# AMP_UN7_T.net
KiCad netlist of a schematic drawn in EAGLE
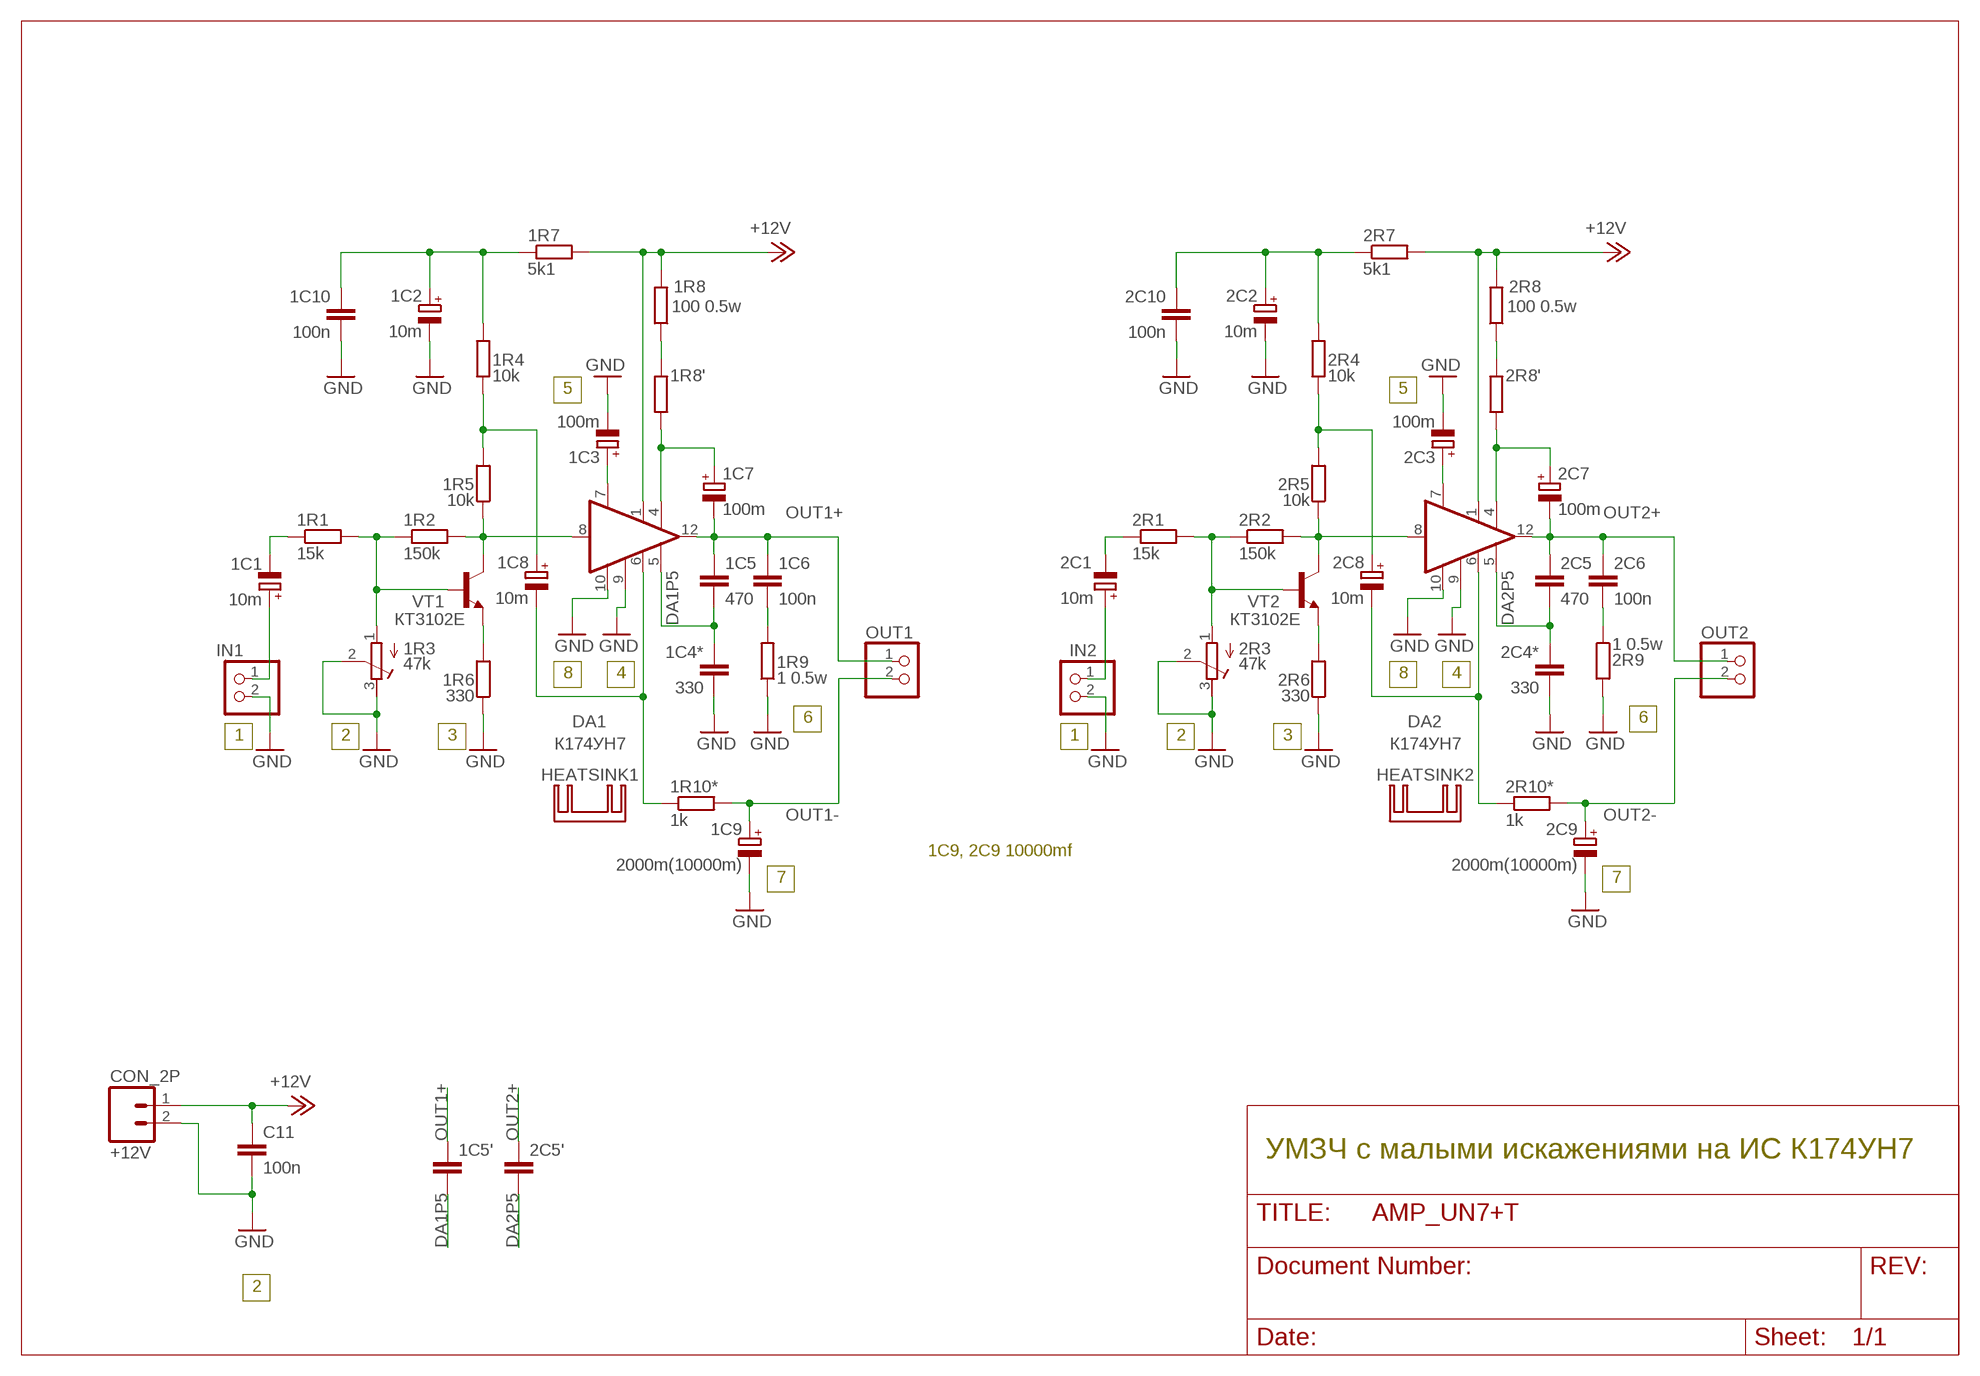
[diagram p0: schematic, sheet 1]

(export (version "E")
  (design (tool "Eeschema 10.0.6"))
  (components
    (comp (ref "+12V")
      (value "CON_2P")
      (footprint "eagle-import:CON_PWR_2PIN4MM")
      (libsource (lib "eagle-import") (part "CON_2P"))
    )
    (comp (ref "1C1")
      (value "10m")
      (footprint "eagle-import:E2,5-5")
      (libsource (lib "eagle-import") (part "CPOL-EUE2.5-5"))
    )
    (comp (ref "1C2")
      (value "10m")
      (footprint "eagle-import:E2,5-5")
      (libsource (lib "eagle-import") (part "CPOL-EUE2.5-5"))
    )
    (comp (ref "1C3")
      (value "100m")
      (footprint "eagle-import:E2,5-6")
      (libsource (lib "eagle-import") (part "CPOL-EUE2.5-6"))
    )
    (comp (ref "1C4*")
      (value "330")
      (footprint "eagle-import:C050-025X075")
      (libsource (lib "eagle-import") (part "C-EU050-025X075"))
    )
    (comp (ref "1C5")
      (value "470")
      (footprint "eagle-import:C050-030X075")
      (libsource (lib "eagle-import") (part "C-EU050-030X075"))
    )
    (comp (ref "1C5'")
      (value "C-EUC0805")
      (footprint "eagle-import:C0805")
      (libsource (lib "eagle-import") (part "C-EUC0805"))
    )
    (comp (ref "1C6")
      (value "100n")
      (footprint "eagle-import:C075-052X106")
      (libsource (lib "eagle-import") (part "C-EU075-052X106"))
    )
    (comp (ref "1C7")
      (value "100m")
      (footprint "eagle-import:E2,5-5")
      (libsource (lib "eagle-import") (part "CPOL-EUE2.5-5"))
    )
    (comp (ref "1C8")
      (value "10m")
      (footprint "eagle-import:E2,5-5")
      (libsource (lib "eagle-import") (part "CPOL-EUE2.5-5"))
    )
    (comp (ref "1C9")
      (value "2000m(10000m)")
      (footprint "eagle-import:E5-13")
      (libsource (lib "eagle-import") (part "CPOL-EUE5-13"))
    )
    (comp (ref "1C10")
      (value "100n")
      (footprint "eagle-import:C0805")
      (libsource (lib "eagle-import") (part "C-EUC0805"))
    )
    (comp (ref "1R1")
      (value "15k")
      (footprint "eagle-import:R0805")
      (libsource (lib "eagle-import") (part "R-EU_R0805"))
    )
    (comp (ref "1R2")
      (value "150k")
      (footprint "eagle-import:R0805")
      (libsource (lib "eagle-import") (part "R-EU_R0805"))
    )
    (comp (ref "1R3")
      (value "47k")
      (footprint "eagle-import:RTRIM3296W")
      (libsource (lib "eagle-import") (part "R-TRIMM3296W"))
    )
    (comp (ref "1R4")
      (value "10k")
      (footprint "eagle-import:R0805")
      (libsource (lib "eagle-import") (part "R-EU_R0805"))
    )
    (comp (ref "1R5")
      (value "10k")
      (footprint "eagle-import:R0805")
      (libsource (lib "eagle-import") (part "R-EU_R0805"))
    )
    (comp (ref "1R6")
      (value "330")
      (footprint "eagle-import:R0805")
      (libsource (lib "eagle-import") (part "R-EU_R0805"))
    )
    (comp (ref "1R7")
      (value "5k1")
      (footprint "eagle-import:R0805")
      (libsource (lib "eagle-import") (part "R-EU_R0805"))
    )
    (comp (ref "1R8")
      (value "100 0.5w")
      (footprint "eagle-import:R1210W")
      (libsource (lib "eagle-import") (part "R-EU_R1210W"))
    )
    (comp (ref "1R8'")
      (value "R-EU_R1210W")
      (footprint "eagle-import:R1210W")
      (libsource (lib "eagle-import") (part "R-EU_R1210W"))
    )
    (comp (ref "1R9")
      (value "1 0.5w")
      (footprint "eagle-import:0411V")
      (libsource (lib "eagle-import") (part "R-EU_0411/3V"))
    )
    (comp (ref "1R10*")
      (value "1k")
      (footprint "eagle-import:0207_12")
      (libsource (lib "eagle-import") (part "R-EU_0207/12"))
    )
    (comp (ref "2C1")
      (value "10m")
      (footprint "eagle-import:E2,5-5")
      (libsource (lib "eagle-import") (part "CPOL-EUE2.5-5"))
    )
    (comp (ref "2C2")
      (value "10m")
      (footprint "eagle-import:E2,5-5")
      (libsource (lib "eagle-import") (part "CPOL-EUE2.5-5"))
    )
    (comp (ref "2C3")
      (value "100m")
      (footprint "eagle-import:E2,5-6")
      (libsource (lib "eagle-import") (part "CPOL-EUE2.5-6"))
    )
    (comp (ref "2C4*")
      (value "330")
      (footprint "eagle-import:C050-025X075")
      (libsource (lib "eagle-import") (part "C-EU050-025X075"))
    )
    (comp (ref "2C5")
      (value "470")
      (footprint "eagle-import:C050-030X075")
      (libsource (lib "eagle-import") (part "C-EU050-030X075"))
    )
    (comp (ref "2C5'")
      (value "C-EUC0805")
      (footprint "eagle-import:C0805")
      (libsource (lib "eagle-import") (part "C-EUC0805"))
    )
    (comp (ref "2C6")
      (value "100n")
      (footprint "eagle-import:C075-052X106")
      (libsource (lib "eagle-import") (part "C-EU075-052X106"))
    )
    (comp (ref "2C7")
      (value "100m")
      (footprint "eagle-import:E2,5-5")
      (libsource (lib "eagle-import") (part "CPOL-EUE2.5-5"))
    )
    (comp (ref "2C8")
      (value "10m")
      (footprint "eagle-import:E2,5-5")
      (libsource (lib "eagle-import") (part "CPOL-EUE2.5-5"))
    )
    (comp (ref "2C9")
      (value "2000m(10000m)")
      (footprint "eagle-import:E5-13")
      (libsource (lib "eagle-import") (part "CPOL-EUE5-13"))
    )
    (comp (ref "2C10")
      (value "100n")
      (footprint "eagle-import:C0805")
      (libsource (lib "eagle-import") (part "C-EUC0805"))
    )
    (comp (ref "2R1")
      (value "15k")
      (footprint "eagle-import:R0805")
      (libsource (lib "eagle-import") (part "R-EU_R0805"))
    )
    (comp (ref "2R2")
      (value "150k")
      (footprint "eagle-import:R0805")
      (libsource (lib "eagle-import") (part "R-EU_R0805"))
    )
    (comp (ref "2R3")
      (value "47k")
      (footprint "eagle-import:RTRIM3296W")
      (libsource (lib "eagle-import") (part "R-TRIMM3296W"))
    )
    (comp (ref "2R4")
      (value "10k")
      (footprint "eagle-import:R0805")
      (libsource (lib "eagle-import") (part "R-EU_R0805"))
    )
    (comp (ref "2R5")
      (value "10k")
      (footprint "eagle-import:R0805")
      (libsource (lib "eagle-import") (part "R-EU_R0805"))
    )
    (comp (ref "2R6")
      (value "330")
      (footprint "eagle-import:R0805")
      (libsource (lib "eagle-import") (part "R-EU_R0805"))
    )
    (comp (ref "2R7")
      (value "5k1")
      (footprint "eagle-import:R0805")
      (libsource (lib "eagle-import") (part "R-EU_R0805"))
    )
    (comp (ref "2R8")
      (value "100 0.5w")
      (footprint "eagle-import:R1210W")
      (libsource (lib "eagle-import") (part "R-EU_R1210W"))
    )
    (comp (ref "2R8'")
      (value "R-EU_R1210W")
      (footprint "eagle-import:R1210W")
      (libsource (lib "eagle-import") (part "R-EU_R1210W"))
    )
    (comp (ref "2R9")
      (value "1 0.5w")
      (footprint "eagle-import:0411V")
      (libsource (lib "eagle-import") (part "R-EU_0411/3V"))
    )
    (comp (ref "2R10*")
      (value "1k")
      (footprint "eagle-import:0207_12")
      (libsource (lib "eagle-import") (part "R-EU_0207/12"))
    )
    (comp (ref "C11")
      (value "100n")
      (footprint "eagle-import:C0805")
      (libsource (lib "eagle-import") (part "C-EUC0805"))
    )
    (comp (ref "DA1")
      (value "К174УН7")
      (footprint "eagle-import:DIL16-12")
      (libsource (lib "eagle-import") (part "K174UN7"))
    )
    (comp (ref "DA2")
      (value "К174УН7")
      (footprint "eagle-import:DIL16-12")
      (libsource (lib "eagle-import") (part "K174UN7"))
    )
    (comp (ref "HEATSINK1")
      (value "HEATSINK_V")
      (footprint "eagle-import:H_VELS")
      (libsource (lib "eagle-import") (part "HEATSINK_V"))
    )
    (comp (ref "HEATSINK2")
      (value "HEATSINK_V")
      (footprint "eagle-import:H_VELS")
      (libsource (lib "eagle-import") (part "HEATSINK_V"))
    )
    (comp (ref "IN1")
      (value "PINHD-1X2")
      (footprint "eagle-import:1X02")
      (libsource (lib "eagle-import") (part "PINHD-1X2"))
    )
    (comp (ref "IN2")
      (value "PINHD-1X2")
      (footprint "eagle-import:1X02")
      (libsource (lib "eagle-import") (part "PINHD-1X2"))
    )
    (comp (ref "OUT1")
      (value "PINHD-1X2")
      (footprint "eagle-import:1X02")
      (libsource (lib "eagle-import") (part "PINHD-1X2"))
    )
    (comp (ref "OUT2")
      (value "PINHD-1X2")
      (footprint "eagle-import:1X02")
      (libsource (lib "eagle-import") (part "PINHD-1X2"))
    )
    (comp (ref "VT1")
      (value "КТ3102Е")
      (footprint "eagle-import:TO92")
      (libsource (lib "eagle-import") (part "BJT_NPN_TO-92_CBE"))
    )
    (comp (ref "VT2")
      (value "КТ3102Е")
      (footprint "eagle-import:TO92")
      (libsource (lib "eagle-import") (part "BJT_NPN_TO-92_CBE"))
    )
  )
  (nets
    (net (code "1") (name "+12V") (class "Default")
      (node (ref "+12V") (pin "1") (pinfunction "1_1") (pintype "passive"))
      (node (ref "1R7") (pin "2") (pinfunction "2_2") (pintype "passive"))
      (node (ref "1R8") (pin "2") (pinfunction "2_2") (pintype "passive"))
      (node (ref "2R7") (pin "2") (pinfunction "2_2") (pintype "passive"))
      (node (ref "2R8") (pin "2") (pinfunction "2_2") (pintype "passive"))
      (node (ref "C11") (pin "1") (pinfunction "1_1") (pintype "passive"))
      (node (ref "DA1") (pin "1") (pinfunction "1+V_1") (pintype "power_in"))
      (node (ref "DA2") (pin "1") (pinfunction "1+V_1") (pintype "power_in"))
    )
    (net (code "2") (name "/DA1P5") (class "Default")
      (node (ref "1C4*") (pin "1") (pinfunction "1_1") (pintype "passive"))
      (node (ref "1C5") (pin "2") (pinfunction "2_2") (pintype "passive"))
      (node (ref "1C5'") (pin "2") (pinfunction "2_2") (pintype "passive"))
      (node (ref "DA1") (pin "5") (pinfunction "5KOR_5") (pintype "passive"))
    )
    (net (code "3") (name "/DA2P5") (class "Default")
      (node (ref "2C4*") (pin "1") (pinfunction "1_1") (pintype "passive"))
      (node (ref "2C5") (pin "2") (pinfunction "2_2") (pintype "passive"))
      (node (ref "2C5'") (pin "2") (pinfunction "2_2") (pintype "passive"))
      (node (ref "DA2") (pin "5") (pinfunction "5KOR_5") (pintype "passive"))
    )
    (net (code "4") (name "/OUT1+") (class "Default")
      (node (ref "1C5") (pin "1") (pinfunction "1_1") (pintype "passive"))
      (node (ref "1C5'") (pin "1") (pinfunction "1_1") (pintype "passive"))
      (node (ref "1C6") (pin "1") (pinfunction "1_1") (pintype "passive"))
      (node (ref "1C7") (pin "-") (pinfunction "-_-") (pintype "passive"))
      (node (ref "DA1") (pin "12") (pinfunction "12OUT_12") (pintype "output"))
      (node (ref "OUT1") (pin "1") (pinfunction "1_1") (pintype "passive"))
    )
    (net (code "5") (name "/OUT1-") (class "Default")
      (node (ref "1C9") (pin "+") (pinfunction "+_+") (pintype "passive"))
      (node (ref "1R10*") (pin "2") (pinfunction "2_2") (pintype "passive"))
      (node (ref "OUT1") (pin "2") (pinfunction "2_2") (pintype "passive"))
    )
    (net (code "6") (name "/OUT2+") (class "Default")
      (node (ref "2C5") (pin "1") (pinfunction "1_1") (pintype "passive"))
      (node (ref "2C5'") (pin "1") (pinfunction "1_1") (pintype "passive"))
      (node (ref "2C6") (pin "1") (pinfunction "1_1") (pintype "passive"))
      (node (ref "2C7") (pin "-") (pinfunction "-_-") (pintype "passive"))
      (node (ref "DA2") (pin "12") (pinfunction "12OUT_12") (pintype "output"))
      (node (ref "OUT2") (pin "1") (pinfunction "1_1") (pintype "passive"))
    )
    (net (code "7") (name "/OUT2-") (class "Default")
      (node (ref "2C9") (pin "+") (pinfunction "+_+") (pintype "passive"))
      (node (ref "2R10*") (pin "2") (pinfunction "2_2") (pintype "passive"))
      (node (ref "OUT2") (pin "2") (pinfunction "2_2") (pintype "passive"))
    )
    (net (code "8") (name "GND") (class "Default")
      (node (ref "+12V") (pin "2") (pinfunction "2_2") (pintype "passive"))
      (node (ref "1C10") (pin "2") (pinfunction "2_2") (pintype "passive"))
      (node (ref "1C2") (pin "-") (pinfunction "-_-") (pintype "passive"))
      (node (ref "1C3") (pin "-") (pinfunction "-_-") (pintype "passive"))
      (node (ref "1C4*") (pin "2") (pinfunction "2_2") (pintype "passive"))
      (node (ref "1C9") (pin "-") (pinfunction "-_-") (pintype "passive"))
      (node (ref "1R3") (pin "2") (pinfunction "S_2") (pintype "passive"))
      (node (ref "1R3") (pin "3") (pinfunction "E_3") (pintype "passive"))
      (node (ref "1R6") (pin "1") (pinfunction "1_1") (pintype "passive"))
      (node (ref "1R9") (pin "1") (pinfunction "1_1") (pintype "passive"))
      (node (ref "2C10") (pin "2") (pinfunction "2_2") (pintype "passive"))
      (node (ref "2C2") (pin "-") (pinfunction "-_-") (pintype "passive"))
      (node (ref "2C3") (pin "-") (pinfunction "-_-") (pintype "passive"))
      (node (ref "2C4*") (pin "2") (pinfunction "2_2") (pintype "passive"))
      (node (ref "2C9") (pin "-") (pinfunction "-_-") (pintype "passive"))
      (node (ref "2R3") (pin "2") (pinfunction "S_2") (pintype "passive"))
      (node (ref "2R3") (pin "3") (pinfunction "E_3") (pintype "passive"))
      (node (ref "2R6") (pin "1") (pinfunction "1_1") (pintype "passive"))
      (node (ref "2R9") (pin "2") (pinfunction "2_2") (pintype "passive"))
      (node (ref "C11") (pin "2") (pinfunction "2_2") (pintype "passive"))
      (node (ref "DA1") (pin "10") (pinfunction "10E_10") (pintype "passive"))
      (node (ref "DA1") (pin "9") (pinfunction "9-V_9") (pintype "power_in"))
      (node (ref "DA2") (pin "10") (pinfunction "10E_10") (pintype "passive"))
      (node (ref "DA2") (pin "9") (pinfunction "9-V_9") (pintype "power_in"))
      (node (ref "IN1") (pin "2") (pinfunction "2_2") (pintype "passive"))
      (node (ref "IN2") (pin "2") (pinfunction "2_2") (pintype "passive"))
    )
    (net (code "9") (name "Net-(1C1-Pad+)") (class "Default")
      (node (ref "1C1") (pin "+") (pinfunction "+_+") (pintype "passive"))
      (node (ref "IN1") (pin "1") (pinfunction "1_1") (pintype "passive"))
    )
    (net (code "10") (name "Net-(1C1-Pad-)") (class "Default")
      (node (ref "1C1") (pin "-") (pinfunction "-_-") (pintype "passive"))
      (node (ref "1R1") (pin "1") (pinfunction "1_1") (pintype "passive"))
    )
    (net (code "11") (name "Net-(1C6-Pad2)") (class "Default")
      (node (ref "1C6") (pin "2") (pinfunction "2_2") (pintype "passive"))
      (node (ref "1R9") (pin "2") (pinfunction "2_2") (pintype "passive"))
    )
    (net (code "12") (name "Net-(1C8-Pad+)") (class "Default")
      (node (ref "1C8") (pin "+") (pinfunction "+_+") (pintype "passive"))
      (node (ref "1R4") (pin "1") (pinfunction "1_1") (pintype "passive"))
      (node (ref "1R5") (pin "2") (pinfunction "2_2") (pintype "passive"))
    )
    (net (code "13") (name "Net-(1C10-Pad1)") (class "Default")
      (node (ref "1C10") (pin "1") (pinfunction "1_1") (pintype "passive"))
      (node (ref "1C2") (pin "+") (pinfunction "+_+") (pintype "passive"))
      (node (ref "1R4") (pin "2") (pinfunction "2_2") (pintype "passive"))
      (node (ref "1R7") (pin "1") (pinfunction "1_1") (pintype "passive"))
    )
    (net (code "14") (name "Net-(1R3-A)") (class "Default")
      (node (ref "1R1") (pin "2") (pinfunction "2_2") (pintype "passive"))
      (node (ref "1R2") (pin "1") (pinfunction "1_1") (pintype "passive"))
      (node (ref "1R3") (pin "1") (pinfunction "A_1") (pintype "passive"))
      (node (ref "VT1") (pin "2") (pinfunction "B_2") (pintype "passive"))
    )
    (net (code "15") (name "Net-(1R8'-Pad2)") (class "Default")
      (node (ref "1R8") (pin "1") (pinfunction "1_1") (pintype "passive"))
      (node (ref "1R8'") (pin "2") (pinfunction "2_2") (pintype "passive"))
    )
    (net (code "16") (name "Net-(2C1-Pad+)") (class "Default")
      (node (ref "2C1") (pin "+") (pinfunction "+_+") (pintype "passive"))
      (node (ref "IN2") (pin "1") (pinfunction "1_1") (pintype "passive"))
    )
    (net (code "17") (name "Net-(2C1-Pad-)") (class "Default")
      (node (ref "2C1") (pin "-") (pinfunction "-_-") (pintype "passive"))
      (node (ref "2R1") (pin "1") (pinfunction "1_1") (pintype "passive"))
    )
    (net (code "18") (name "Net-(2C6-Pad2)") (class "Default")
      (node (ref "2C6") (pin "2") (pinfunction "2_2") (pintype "passive"))
      (node (ref "2R9") (pin "1") (pinfunction "1_1") (pintype "passive"))
    )
    (net (code "19") (name "Net-(2C8-Pad+)") (class "Default")
      (node (ref "2C8") (pin "+") (pinfunction "+_+") (pintype "passive"))
      (node (ref "2R4") (pin "1") (pinfunction "1_1") (pintype "passive"))
      (node (ref "2R5") (pin "2") (pinfunction "2_2") (pintype "passive"))
    )
    (net (code "20") (name "Net-(2C10-Pad1)") (class "Default")
      (node (ref "2C10") (pin "1") (pinfunction "1_1") (pintype "passive"))
      (node (ref "2C2") (pin "+") (pinfunction "+_+") (pintype "passive"))
      (node (ref "2R4") (pin "2") (pinfunction "2_2") (pintype "passive"))
      (node (ref "2R7") (pin "1") (pinfunction "1_1") (pintype "passive"))
    )
    (net (code "21") (name "Net-(2R3-A)") (class "Default")
      (node (ref "2R1") (pin "2") (pinfunction "2_2") (pintype "passive"))
      (node (ref "2R2") (pin "1") (pinfunction "1_1") (pintype "passive"))
      (node (ref "2R3") (pin "1") (pinfunction "A_1") (pintype "passive"))
      (node (ref "VT2") (pin "2") (pinfunction "B_2") (pintype "passive"))
    )
    (net (code "22") (name "Net-(2R8'-Pad2)") (class "Default")
      (node (ref "2R8") (pin "1") (pinfunction "1_1") (pintype "passive"))
      (node (ref "2R8'") (pin "2") (pinfunction "2_2") (pintype "passive"))
    )
    (net (code "23") (name "Net-(DA1-4++U)") (class "Default")
      (node (ref "1C7") (pin "+") (pinfunction "+_+") (pintype "passive"))
      (node (ref "1R8'") (pin "1") (pinfunction "1_1") (pintype "passive"))
      (node (ref "DA1") (pin "4") (pinfunction "4++U_4") (pintype "passive"))
    )
    (net (code "24") (name "Net-(DA1-6FB)") (class "Default")
      (node (ref "1C8") (pin "-") (pinfunction "-_-") (pintype "passive"))
      (node (ref "1R10*") (pin "1") (pinfunction "1_1") (pintype "passive"))
      (node (ref "DA1") (pin "6") (pinfunction "6FB_6") (pintype "passive"))
    )
    (net (code "25") (name "Net-(DA1-7FILTR)") (class "Default")
      (node (ref "1C3") (pin "+") (pinfunction "+_+") (pintype "passive"))
      (node (ref "DA1") (pin "7") (pinfunction "7FILTR_7") (pintype "passive"))
    )
    (net (code "26") (name "Net-(DA1-8IN)") (class "Default")
      (node (ref "1R2") (pin "2") (pinfunction "2_2") (pintype "passive"))
      (node (ref "1R5") (pin "1") (pinfunction "1_1") (pintype "passive"))
      (node (ref "DA1") (pin "8") (pinfunction "8IN_8") (pintype "input"))
      (node (ref "VT1") (pin "1") (pinfunction "C_1") (pintype "passive"))
    )
    (net (code "27") (name "Net-(DA2-4++U)") (class "Default")
      (node (ref "2C7") (pin "+") (pinfunction "+_+") (pintype "passive"))
      (node (ref "2R8'") (pin "1") (pinfunction "1_1") (pintype "passive"))
      (node (ref "DA2") (pin "4") (pinfunction "4++U_4") (pintype "passive"))
    )
    (net (code "28") (name "Net-(DA2-6FB)") (class "Default")
      (node (ref "2C8") (pin "-") (pinfunction "-_-") (pintype "passive"))
      (node (ref "2R10*") (pin "1") (pinfunction "1_1") (pintype "passive"))
      (node (ref "DA2") (pin "6") (pinfunction "6FB_6") (pintype "passive"))
    )
    (net (code "29") (name "Net-(DA2-7FILTR)") (class "Default")
      (node (ref "2C3") (pin "+") (pinfunction "+_+") (pintype "passive"))
      (node (ref "DA2") (pin "7") (pinfunction "7FILTR_7") (pintype "passive"))
    )
    (net (code "30") (name "Net-(DA2-8IN)") (class "Default")
      (node (ref "2R2") (pin "2") (pinfunction "2_2") (pintype "passive"))
      (node (ref "2R5") (pin "1") (pinfunction "1_1") (pintype "passive"))
      (node (ref "DA2") (pin "8") (pinfunction "8IN_8") (pintype "input"))
      (node (ref "VT2") (pin "1") (pinfunction "C_1") (pintype "passive"))
    )
    (net (code "31") (name "Net-(VT1-E)") (class "Default")
      (node (ref "1R6") (pin "2") (pinfunction "2_2") (pintype "passive"))
      (node (ref "VT1") (pin "3") (pinfunction "E_3") (pintype "passive"))
    )
    (net (code "32") (name "Net-(VT2-E)") (class "Default")
      (node (ref "2R6") (pin "2") (pinfunction "2_2") (pintype "passive"))
      (node (ref "VT2") (pin "3") (pinfunction "E_3") (pintype "passive"))
    )
  )
)
